# MotorControl.net
KiCad netlist of a schematic drawn in Altium Designer
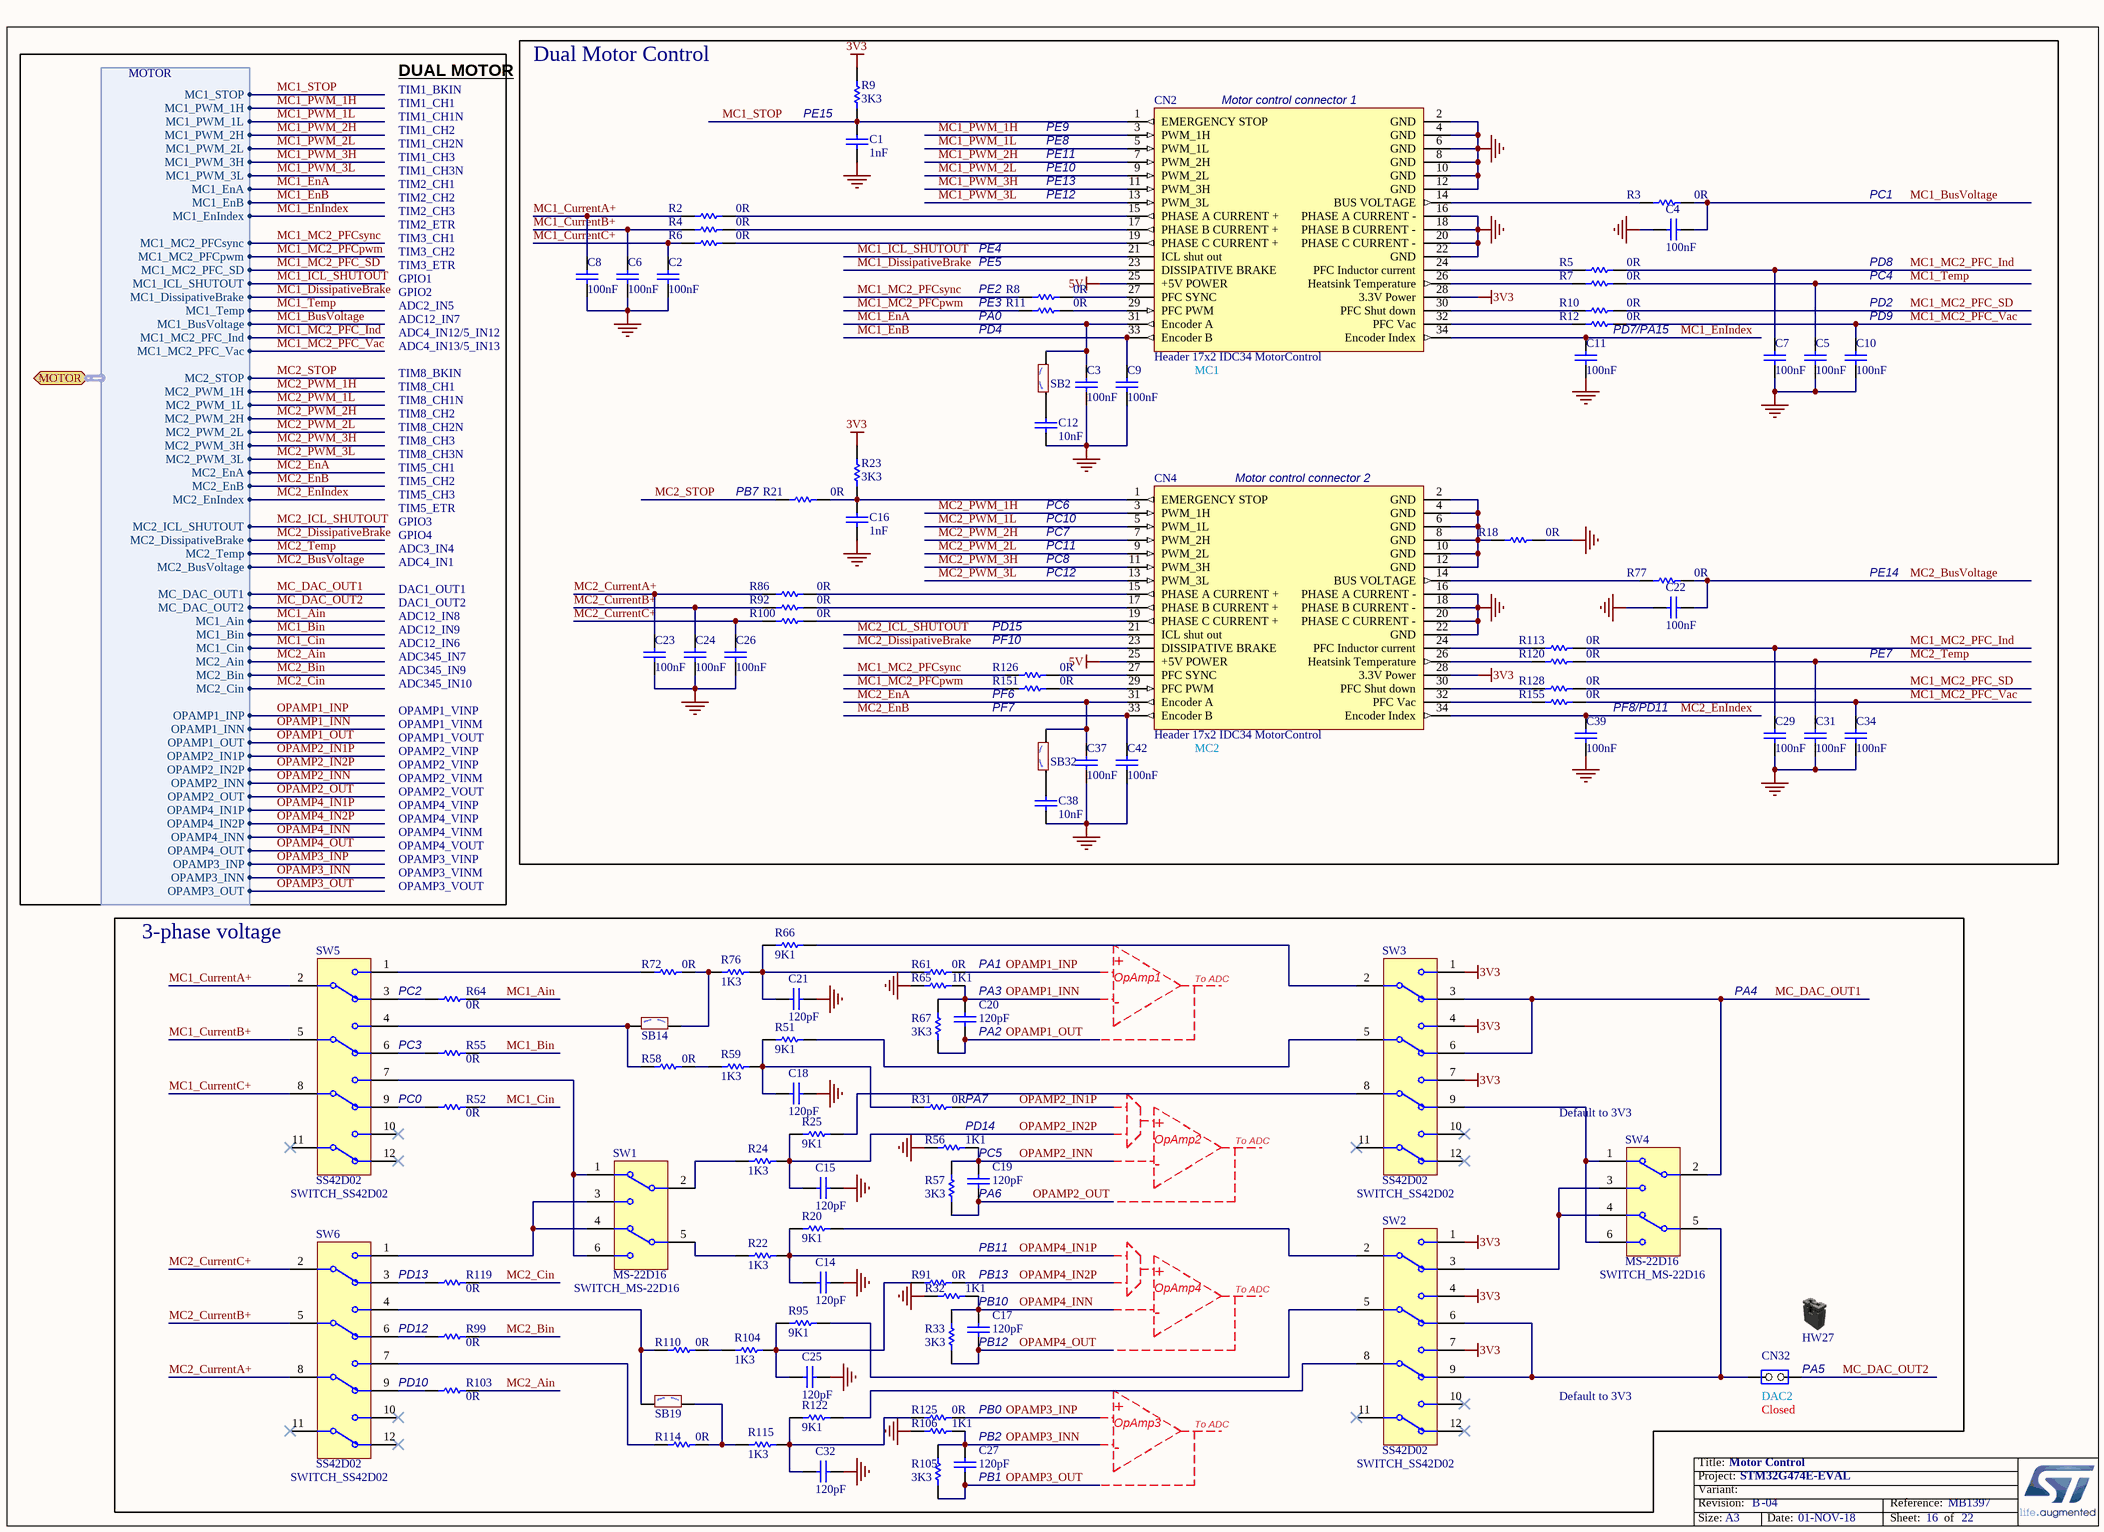
[diagram p0: MotorControl.SchDoc]

(export (version "E")
  (design (tool "Eeschema 10.0.6"))
  (components
    (comp (ref "C1")
      (value "1nF")
      (footprint "C0402")
      (description "Capacitor, MLCC, 1nF, 16V, X7R, 10%, 0402, T=0.5mm")
      (fields
        (field (name "INTERNAL_PART_NUMBER") "MCD-00198")
        (field (name "MANUFACTURER_PART_NUMBER") "CC0402KRX7R7BB102")
        (field (name "PROVIDED_BY") "SUBCO")
      )
      (libsource (lib "MCD_PARTS_database") (part "Capacitor"))
    )
    (comp (ref "C2")
      (value "100nF")
      (footprint "C0402")
      (description "Capacitor, MLCC, 100nF, 16V, X7R, 10%, 0402, T=0.5mm")
      (fields
        (field (name "INTERNAL_PART_NUMBER") "MCD-00006")
        (field (name "MANUFACTURER_PART_NUMBER") "CC0402KRX7R7BB104")
        (field (name "PROVIDED_BY") "SUBCO")
      )
      (libsource (lib "MCD_PARTS_database") (part "Capacitor"))
    )
    (comp (ref "C3")
      (value "100nF")
      (footprint "C0402")
      (description "Capacitor, MLCC, 100nF, 16V, X7R, 10%, 0402, T=0.5mm")
      (fields
        (field (name "INTERNAL_PART_NUMBER") "MCD-00006")
        (field (name "MANUFACTURER_PART_NUMBER") "CC0402KRX7R7BB104")
        (field (name "PROVIDED_BY") "SUBCO")
      )
      (libsource (lib "MCD_PARTS_database") (part "Capacitor"))
    )
    (comp (ref "C4")
      (value "100nF")
      (footprint "C0402")
      (description "Capacitor, MLCC, 100nF, 16V, X7R, 10%, 0402, T=0.5mm")
      (fields
        (field (name "INTERNAL_PART_NUMBER") "MCD-00006")
        (field (name "MANUFACTURER_PART_NUMBER") "CC0402KRX7R7BB104")
        (field (name "PROVIDED_BY") "SUBCO")
      )
      (libsource (lib "MCD_PARTS_database") (part "Capacitor"))
    )
    (comp (ref "C5")
      (value "100nF")
      (footprint "C0402")
      (description "Capacitor, MLCC, 100nF, 16V, X7R, 10%, 0402, T=0.5mm")
      (fields
        (field (name "INTERNAL_PART_NUMBER") "MCD-00006")
        (field (name "MANUFACTURER_PART_NUMBER") "CC0402KRX7R7BB104")
        (field (name "PROVIDED_BY") "SUBCO")
      )
      (libsource (lib "MCD_PARTS_database") (part "Capacitor"))
    )
    (comp (ref "C6")
      (value "100nF")
      (footprint "C0402")
      (description "Capacitor, MLCC, 100nF, 16V, X7R, 10%, 0402, T=0.5mm")
      (fields
        (field (name "INTERNAL_PART_NUMBER") "MCD-00006")
        (field (name "MANUFACTURER_PART_NUMBER") "CC0402KRX7R7BB104")
        (field (name "PROVIDED_BY") "SUBCO")
      )
      (libsource (lib "MCD_PARTS_database") (part "Capacitor"))
    )
    (comp (ref "C7")
      (value "100nF")
      (footprint "C0402")
      (description "Capacitor, MLCC, 100nF, 16V, X7R, 10%, 0402, T=0.5mm")
      (fields
        (field (name "INTERNAL_PART_NUMBER") "MCD-00006")
        (field (name "MANUFACTURER_PART_NUMBER") "CC0402KRX7R7BB104")
        (field (name "PROVIDED_BY") "SUBCO")
      )
      (libsource (lib "MCD_PARTS_database") (part "Capacitor"))
    )
    (comp (ref "C8")
      (value "100nF")
      (footprint "C0402")
      (description "Capacitor, MLCC, 100nF, 16V, X7R, 10%, 0402, T=0.5mm")
      (fields
        (field (name "INTERNAL_PART_NUMBER") "MCD-00006")
        (field (name "MANUFACTURER_PART_NUMBER") "CC0402KRX7R7BB104")
        (field (name "PROVIDED_BY") "SUBCO")
      )
      (libsource (lib "MCD_PARTS_database") (part "Capacitor"))
    )
    (comp (ref "C9")
      (value "100nF")
      (footprint "C0402")
      (description "Capacitor, MLCC, 100nF, 16V, X7R, 10%, 0402, T=0.5mm")
      (fields
        (field (name "INTERNAL_PART_NUMBER") "MCD-00006")
        (field (name "MANUFACTURER_PART_NUMBER") "CC0402KRX7R7BB104")
        (field (name "PROVIDED_BY") "SUBCO")
      )
      (libsource (lib "MCD_PARTS_database") (part "Capacitor"))
    )
    (comp (ref "C10")
      (value "100nF")
      (footprint "C0402")
      (description "Capacitor, MLCC, 100nF, 16V, X7R, 10%, 0402, T=0.5mm")
      (fields
        (field (name "INTERNAL_PART_NUMBER") "MCD-00006")
        (field (name "MANUFACTURER_PART_NUMBER") "CC0402KRX7R7BB104")
        (field (name "PROVIDED_BY") "SUBCO")
      )
      (libsource (lib "MCD_PARTS_database") (part "Capacitor"))
    )
    (comp (ref "C11")
      (value "100nF")
      (footprint "C0402")
      (description "Capacitor, MLCC, 100nF, 16V, X7R, 10%, 0402, T=0.5mm")
      (fields
        (field (name "INTERNAL_PART_NUMBER") "MCD-00006")
        (field (name "MANUFACTURER_PART_NUMBER") "CC0402KRX7R7BB104")
        (field (name "PROVIDED_BY") "SUBCO")
      )
      (libsource (lib "MCD_PARTS_database") (part "Capacitor"))
    )
    (comp (ref "C12")
      (value "10nF")
      (footprint "C0402")
      (description "Capacitor, MLCC, 10nF, 16V, X7R, 10%, 0402, T=0.5mm")
      (fields
        (field (name "INTERNAL_PART_NUMBER") "MCD-00011")
        (field (name "MANUFACTURER_PART_NUMBER") "CC0402KRX7R7BB103")
        (field (name "PROVIDED_BY") "SUBCO")
      )
      (libsource (lib "MCD_PARTS_database") (part "Capacitor"))
    )
    (comp (ref "C14")
      (value "120pF")
      (footprint "C0603")
      (description "Capacitor,120pF,50V,NPO,5%,0603")
      (fields
        (field (name "INTERNAL_PART_NUMBER") "MCD-01188")
        (field (name "MANUFACTURER_PART_NUMBER") "CC0603JRNPO9BN121")
        (field (name "PROVIDED_BY") "SUBCO")
      )
      (libsource (lib "MCD_PARTS_database") (part "Capacitor"))
    )
    (comp (ref "C15")
      (value "120pF")
      (footprint "C0603")
      (description "Capacitor,120pF,50V,NPO,5%,0603")
      (fields
        (field (name "INTERNAL_PART_NUMBER") "MCD-01188")
        (field (name "MANUFACTURER_PART_NUMBER") "CC0603JRNPO9BN121")
        (field (name "PROVIDED_BY") "SUBCO")
      )
      (libsource (lib "MCD_PARTS_database") (part "Capacitor"))
    )
    (comp (ref "C16")
      (value "1nF")
      (footprint "C0402")
      (description "Capacitor, MLCC, 1nF, 16V, X7R, 10%, 0402, T=0.5mm")
      (fields
        (field (name "INTERNAL_PART_NUMBER") "MCD-00198")
        (field (name "MANUFACTURER_PART_NUMBER") "CC0402KRX7R7BB102")
        (field (name "PROVIDED_BY") "SUBCO")
      )
      (libsource (lib "MCD_PARTS_database") (part "Capacitor"))
    )
    (comp (ref "C17")
      (value "120pF")
      (footprint "C0603")
      (description "Capacitor,120pF,50V,NPO,5%,0603")
      (fields
        (field (name "INTERNAL_PART_NUMBER") "MCD-01188")
        (field (name "MANUFACTURER_PART_NUMBER") "CC0603JRNPO9BN121")
        (field (name "PROVIDED_BY") "SUBCO")
      )
      (libsource (lib "MCD_PARTS_database") (part "Capacitor"))
    )
    (comp (ref "C18")
      (value "120pF")
      (footprint "C0603")
      (description "Capacitor,120pF,50V,NPO,5%,0603")
      (fields
        (field (name "INTERNAL_PART_NUMBER") "MCD-01188")
        (field (name "MANUFACTURER_PART_NUMBER") "CC0603JRNPO9BN121")
        (field (name "PROVIDED_BY") "SUBCO")
      )
      (libsource (lib "MCD_PARTS_database") (part "Capacitor"))
    )
    (comp (ref "C19")
      (value "120pF")
      (footprint "C0603")
      (description "Capacitor,120pF,50V,NPO,5%,0603")
      (fields
        (field (name "INTERNAL_PART_NUMBER") "MCD-01188")
        (field (name "MANUFACTURER_PART_NUMBER") "CC0603JRNPO9BN121")
        (field (name "PROVIDED_BY") "SUBCO")
      )
      (libsource (lib "MCD_PARTS_database") (part "Capacitor"))
    )
    (comp (ref "C20")
      (value "120pF")
      (footprint "C0603")
      (description "Capacitor,120pF,50V,NPO,5%,0603")
      (fields
        (field (name "INTERNAL_PART_NUMBER") "MCD-01188")
        (field (name "MANUFACTURER_PART_NUMBER") "CC0603JRNPO9BN121")
        (field (name "PROVIDED_BY") "SUBCO")
      )
      (libsource (lib "MCD_PARTS_database") (part "Capacitor"))
    )
    (comp (ref "C21")
      (value "120pF")
      (footprint "C0603")
      (description "Capacitor,120pF,50V,NPO,5%,0603")
      (fields
        (field (name "INTERNAL_PART_NUMBER") "MCD-01188")
        (field (name "MANUFACTURER_PART_NUMBER") "CC0603JRNPO9BN121")
        (field (name "PROVIDED_BY") "SUBCO")
      )
      (libsource (lib "MCD_PARTS_database") (part "Capacitor"))
    )
    (comp (ref "C22")
      (value "100nF")
      (footprint "C0402")
      (description "Capacitor, MLCC, 100nF, 16V, X7R, 10%, 0402, T=0.5mm")
      (fields
        (field (name "INTERNAL_PART_NUMBER") "MCD-00006")
        (field (name "MANUFACTURER_PART_NUMBER") "CC0402KRX7R7BB104")
        (field (name "PROVIDED_BY") "SUBCO")
      )
      (libsource (lib "MCD_PARTS_database") (part "Capacitor"))
    )
    (comp (ref "C23")
      (value "100nF")
      (footprint "C0402")
      (description "Capacitor, MLCC, 100nF, 16V, X7R, 10%, 0402, T=0.5mm")
      (fields
        (field (name "INTERNAL_PART_NUMBER") "MCD-00006")
        (field (name "MANUFACTURER_PART_NUMBER") "CC0402KRX7R7BB104")
        (field (name "PROVIDED_BY") "SUBCO")
      )
      (libsource (lib "MCD_PARTS_database") (part "Capacitor"))
    )
    (comp (ref "C24")
      (value "100nF")
      (footprint "C0402")
      (description "Capacitor, MLCC, 100nF, 16V, X7R, 10%, 0402, T=0.5mm")
      (fields
        (field (name "INTERNAL_PART_NUMBER") "MCD-00006")
        (field (name "MANUFACTURER_PART_NUMBER") "CC0402KRX7R7BB104")
        (field (name "PROVIDED_BY") "SUBCO")
      )
      (libsource (lib "MCD_PARTS_database") (part "Capacitor"))
    )
    (comp (ref "C25")
      (value "120pF")
      (footprint "C0603")
      (description "Capacitor,120pF,50V,NPO,5%,0603")
      (fields
        (field (name "INTERNAL_PART_NUMBER") "MCD-01188")
        (field (name "MANUFACTURER_PART_NUMBER") "CC0603JRNPO9BN121")
        (field (name "PROVIDED_BY") "SUBCO")
      )
      (libsource (lib "MCD_PARTS_database") (part "Capacitor"))
    )
    (comp (ref "C26")
      (value "100nF")
      (footprint "C0402")
      (description "Capacitor, MLCC, 100nF, 16V, X7R, 10%, 0402, T=0.5mm")
      (fields
        (field (name "INTERNAL_PART_NUMBER") "MCD-00006")
        (field (name "MANUFACTURER_PART_NUMBER") "CC0402KRX7R7BB104")
        (field (name "PROVIDED_BY") "SUBCO")
      )
      (libsource (lib "MCD_PARTS_database") (part "Capacitor"))
    )
    (comp (ref "C27")
      (value "120pF")
      (footprint "C0603")
      (description "Capacitor,120pF,50V,NPO,5%,0603")
      (fields
        (field (name "INTERNAL_PART_NUMBER") "MCD-01188")
        (field (name "MANUFACTURER_PART_NUMBER") "CC0603JRNPO9BN121")
        (field (name "PROVIDED_BY") "SUBCO")
      )
      (libsource (lib "MCD_PARTS_database") (part "Capacitor"))
    )
    (comp (ref "C29")
      (value "100nF")
      (footprint "C0402")
      (description "Capacitor, MLCC, 100nF, 16V, X7R, 10%, 0402, T=0.5mm")
      (fields
        (field (name "INTERNAL_PART_NUMBER") "MCD-00006")
        (field (name "MANUFACTURER_PART_NUMBER") "CC0402KRX7R7BB104")
        (field (name "PROVIDED_BY") "SUBCO")
      )
      (libsource (lib "MCD_PARTS_database") (part "Capacitor"))
    )
    (comp (ref "C31")
      (value "100nF")
      (footprint "C0402")
      (description "Capacitor, MLCC, 100nF, 16V, X7R, 10%, 0402, T=0.5mm")
      (fields
        (field (name "INTERNAL_PART_NUMBER") "MCD-00006")
        (field (name "MANUFACTURER_PART_NUMBER") "CC0402KRX7R7BB104")
        (field (name "PROVIDED_BY") "SUBCO")
      )
      (libsource (lib "MCD_PARTS_database") (part "Capacitor"))
    )
    (comp (ref "C32")
      (value "120pF")
      (footprint "C0603")
      (description "Capacitor,120pF,50V,NPO,5%,0603")
      (fields
        (field (name "INTERNAL_PART_NUMBER") "MCD-01188")
        (field (name "MANUFACTURER_PART_NUMBER") "CC0603JRNPO9BN121")
        (field (name "PROVIDED_BY") "SUBCO")
      )
      (libsource (lib "MCD_PARTS_database") (part "Capacitor"))
    )
    (comp (ref "C34")
      (value "100nF")
      (footprint "C0402")
      (description "Capacitor, MLCC, 100nF, 16V, X7R, 10%, 0402, T=0.5mm")
      (fields
        (field (name "INTERNAL_PART_NUMBER") "MCD-00006")
        (field (name "MANUFACTURER_PART_NUMBER") "CC0402KRX7R7BB104")
        (field (name "PROVIDED_BY") "SUBCO")
      )
      (libsource (lib "MCD_PARTS_database") (part "Capacitor"))
    )
    (comp (ref "C37")
      (value "100nF")
      (footprint "C0402")
      (description "Capacitor, MLCC, 100nF, 16V, X7R, 10%, 0402, T=0.5mm")
      (fields
        (field (name "INTERNAL_PART_NUMBER") "MCD-00006")
        (field (name "MANUFACTURER_PART_NUMBER") "CC0402KRX7R7BB104")
        (field (name "PROVIDED_BY") "SUBCO")
      )
      (libsource (lib "MCD_PARTS_database") (part "Capacitor"))
    )
    (comp (ref "C38")
      (value "10nF")
      (footprint "C0402")
      (description "Capacitor, MLCC, 10nF, 16V, X7R, 10%, 0402, T=0.5mm")
      (fields
        (field (name "INTERNAL_PART_NUMBER") "MCD-00011")
        (field (name "MANUFACTURER_PART_NUMBER") "CC0402KRX7R7BB103")
        (field (name "PROVIDED_BY") "SUBCO")
      )
      (libsource (lib "MCD_PARTS_database") (part "Capacitor"))
    )
    (comp (ref "C39")
      (value "100nF")
      (footprint "C0402")
      (description "Capacitor, MLCC, 100nF, 16V, X7R, 10%, 0402, T=0.5mm")
      (fields
        (field (name "INTERNAL_PART_NUMBER") "MCD-00006")
        (field (name "MANUFACTURER_PART_NUMBER") "CC0402KRX7R7BB104")
        (field (name "PROVIDED_BY") "SUBCO")
      )
      (libsource (lib "MCD_PARTS_database") (part "Capacitor"))
    )
    (comp (ref "C42")
      (value "100nF")
      (footprint "C0402")
      (description "Capacitor, MLCC, 100nF, 16V, X7R, 10%, 0402, T=0.5mm")
      (fields
        (field (name "INTERNAL_PART_NUMBER") "MCD-00006")
        (field (name "MANUFACTURER_PART_NUMBER") "CC0402KRX7R7BB104")
        (field (name "PROVIDED_BY") "SUBCO")
      )
      (libsource (lib "MCD_PARTS_database") (part "Capacitor"))
    )
    (comp (ref "CN2")
      (value "Header 17x2 IDC34 MotorControl")
      (footprint "CON_SAMTEC_TST-117-01-T-D")
      (description "Header, 17x2, 2.54mm, VR, TH, Height 8.89mm/2.92mm, shrouded")
      (fields
        (field (name "INTERNAL_PART_NUMBER") "MCD-00583")
        (field (name "MANUFACTURER_PART_NUMBER") "TST-117-01-T-D")
        (field (name "PROVIDED_BY") "SUBCO")
      )
      (libsource (lib "MCD_PARTS_database") (part "Header 17x2 IDC34 MotorControl"))
    )
    (comp (ref "CN4")
      (value "Header 17x2 IDC34 MotorControl")
      (footprint "CON_SAMTEC_TST-117-01-T-D")
      (description "Header, 17x2, 2.54mm, VR, TH, Height 8.89mm/2.92mm, shrouded")
      (fields
        (field (name "INTERNAL_PART_NUMBER") "MCD-00583")
        (field (name "MANUFACTURER_PART_NUMBER") "TST-117-01-T-D")
        (field (name "PROVIDED_BY") "SUBCO")
      )
      (libsource (lib "MCD_PARTS_database") (part "Header 17x2 IDC34 MotorControl"))
    )
    (comp (ref "CN32")
      (value "Jumper_Header 2x1")
      (footprint "CON_SAMTEC_TSW-102-07-G-S")
      (description "Header, 2x1, 2,54mm, VR, TH, Height 5.84mm/2.54mm")
      (fields
        (field (name "INTERNAL_PART_NUMBER") "MCD-00045")
        (field (name "MANUFACTURER_PART_NUMBER") "TSW-102-07-x-S")
        (field (name "PROVIDED_BY") "SUBCO")
      )
      (libsource (lib "MCD_PARTS_database") (part "Jumper_Header 2x1"))
    )
    (comp (ref "HW27")
      (value "Shunt Black 2.54mm")
      (description "SHUNT 2.54mm BLACK")
      (fields
        (field (name "INTERNAL_PART_NUMBER") "MCD-00043")
        (field (name "MANUFACTURER_PART_NUMBER") "SNT-100-BK-G")
        (field (name "PROVIDED_BY") "SUBCO")
      )
      (libsource (lib "MCD_PARTS_database") (part "Shunt Black 2.54mm"))
    )
    (comp (ref "R2")
      (value "0R")
      (footprint "R0603")
      (description "Resistor,0R,0603,5%,1/10W")
      (fields
        (field (name "INTERNAL_PART_NUMBER") "MCD-00056")
        (field (name "MANUFACTURER_PART_NUMBER") "RC0603JR-070RL")
        (field (name "PROVIDED_BY") "SUBCO")
      )
      (libsource (lib "MCD_PARTS_database") (part "Resistor"))
    )
    (comp (ref "R3")
      (value "0R")
      (footprint "R0603")
      (description "Resistor,0R,0603,5%,1/10W")
      (fields
        (field (name "INTERNAL_PART_NUMBER") "MCD-00056")
        (field (name "MANUFACTURER_PART_NUMBER") "RC0603JR-070RL")
        (field (name "PROVIDED_BY") "SUBCO")
      )
      (libsource (lib "MCD_PARTS_database") (part "Resistor"))
    )
    (comp (ref "R4")
      (value "0R")
      (footprint "R0603")
      (description "Resistor,0R,0603,5%,1/10W")
      (fields
        (field (name "INTERNAL_PART_NUMBER") "MCD-00056")
        (field (name "MANUFACTURER_PART_NUMBER") "RC0603JR-070RL")
        (field (name "PROVIDED_BY") "SUBCO")
      )
      (libsource (lib "MCD_PARTS_database") (part "Resistor"))
    )
    (comp (ref "R5")
      (value "0R")
      (footprint "R0603")
      (description "Resistor,0R,0603,5%,1/10W")
      (fields
        (field (name "INTERNAL_PART_NUMBER") "MCD-00056")
        (field (name "MANUFACTURER_PART_NUMBER") "RC0603JR-070RL")
        (field (name "PROVIDED_BY") "SUBCO")
      )
      (libsource (lib "MCD_PARTS_database") (part "Resistor"))
    )
    (comp (ref "R6")
      (value "0R")
      (footprint "R0603")
      (description "Resistor,0R,0603,5%,1/10W")
      (fields
        (field (name "INTERNAL_PART_NUMBER") "MCD-00056")
        (field (name "MANUFACTURER_PART_NUMBER") "RC0603JR-070RL")
        (field (name "PROVIDED_BY") "SUBCO")
      )
      (libsource (lib "MCD_PARTS_database") (part "Resistor"))
    )
    (comp (ref "R7")
      (value "0R")
      (footprint "R0603")
      (description "Resistor,0R,0603,5%,1/10W")
      (fields
        (field (name "INTERNAL_PART_NUMBER") "MCD-00056")
        (field (name "MANUFACTURER_PART_NUMBER") "RC0603JR-070RL")
        (field (name "PROVIDED_BY") "SUBCO")
      )
      (libsource (lib "MCD_PARTS_database") (part "Resistor"))
    )
    (comp (ref "R8")
      (value "0R")
      (footprint "R0603")
      (description "Resistor,0R,0603,5%,1/10W")
      (fields
        (field (name "INTERNAL_PART_NUMBER") "MCD-00056")
        (field (name "MANUFACTURER_PART_NUMBER") "RC0603JR-070RL")
        (field (name "PROVIDED_BY") "SUBCO")
      )
      (libsource (lib "MCD_PARTS_database") (part "Resistor"))
    )
    (comp (ref "R9")
      (value "3K3")
      (footprint "R0402")
      (description "Resistor,3K3,0402,1%,1/16W")
      (fields
        (field (name "INTERNAL_PART_NUMBER") "MCD-00184")
        (field (name "MANUFACTURER_PART_NUMBER") "RC0402FR-073K3L")
        (field (name "PROVIDED_BY") "SUBCO")
      )
      (libsource (lib "MCD_PARTS_database") (part "Resistor"))
    )
    (comp (ref "R10")
      (value "0R")
      (footprint "R0603")
      (description "Resistor,0R,0603,5%,1/10W")
      (fields
        (field (name "INTERNAL_PART_NUMBER") "MCD-00056")
        (field (name "MANUFACTURER_PART_NUMBER") "RC0603JR-070RL")
        (field (name "PROVIDED_BY") "SUBCO")
      )
      (libsource (lib "MCD_PARTS_database") (part "Resistor"))
    )
    (comp (ref "R11")
      (value "0R")
      (footprint "R0603")
      (description "Resistor,0R,0603,5%,1/10W")
      (fields
        (field (name "INTERNAL_PART_NUMBER") "MCD-00056")
        (field (name "MANUFACTURER_PART_NUMBER") "RC0603JR-070RL")
        (field (name "PROVIDED_BY") "SUBCO")
      )
      (libsource (lib "MCD_PARTS_database") (part "Resistor"))
    )
    (comp (ref "R12")
      (value "0R")
      (footprint "R0603")
      (description "Resistor,0R,0603,5%,1/10W")
      (fields
        (field (name "INTERNAL_PART_NUMBER") "MCD-00056")
        (field (name "MANUFACTURER_PART_NUMBER") "RC0603JR-070RL")
        (field (name "PROVIDED_BY") "SUBCO")
      )
      (libsource (lib "MCD_PARTS_database") (part "Resistor"))
    )
    (comp (ref "R18")
      (value "0R")
      (footprint "R0603")
      (description "Resistor,0R,0603,5%,1/10W")
      (fields
        (field (name "INTERNAL_PART_NUMBER") "MCD-00056")
        (field (name "MANUFACTURER_PART_NUMBER") "RC0603JR-070RL")
        (field (name "PROVIDED_BY") "SUBCO")
      )
      (libsource (lib "MCD_PARTS_database") (part "Resistor"))
    )
    (comp (ref "R20")
      (value "9K1")
      (footprint "R0603")
      (description "Resistor,9K1,0603,1%,1/10W")
      (fields
        (field (name "INTERNAL_PART_NUMBER") "MCD-00540")
        (field (name "MANUFACTURER_PART_NUMBER") "RC0603FR-079K1L")
        (field (name "PROVIDED_BY") "SUBCO")
      )
      (libsource (lib "MCD_PARTS_database") (part "Resistor"))
    )
    (comp (ref "R21")
      (value "0R")
      (footprint "R0603")
      (description "Resistor,0R,0603,5%,1/10W")
      (fields
        (field (name "INTERNAL_PART_NUMBER") "MCD-00056")
        (field (name "MANUFACTURER_PART_NUMBER") "RC0603JR-070RL")
        (field (name "PROVIDED_BY") "SUBCO")
      )
      (libsource (lib "MCD_PARTS_database") (part "Resistor"))
    )
    (comp (ref "R22")
      (value "1K3")
      (footprint "R0603")
      (description "Resistor,1K3,0603,1%,1/10W")
      (fields
        (field (name "INTERNAL_PART_NUMBER") "MCD-00382")
        (field (name "MANUFACTURER_PART_NUMBER") "RC0603FR-071K3L")
        (field (name "PROVIDED_BY") "SUBCO")
      )
      (libsource (lib "MCD_PARTS_database") (part "Resistor"))
    )
    (comp (ref "R23")
      (value "3K3")
      (footprint "R0402")
      (description "Resistor,3K3,0402,1%,1/16W")
      (fields
        (field (name "INTERNAL_PART_NUMBER") "MCD-00184")
        (field (name "MANUFACTURER_PART_NUMBER") "RC0402FR-073K3L")
        (field (name "PROVIDED_BY") "SUBCO")
      )
      (libsource (lib "MCD_PARTS_database") (part "Resistor"))
    )
    (comp (ref "R24")
      (value "1K3")
      (footprint "R0603")
      (description "Resistor,1K3,0603,1%,1/10W")
      (fields
        (field (name "INTERNAL_PART_NUMBER") "MCD-00382")
        (field (name "MANUFACTURER_PART_NUMBER") "RC0603FR-071K3L")
        (field (name "PROVIDED_BY") "SUBCO")
      )
      (libsource (lib "MCD_PARTS_database") (part "Resistor"))
    )
    (comp (ref "R25")
      (value "9K1")
      (footprint "R0603")
      (description "Resistor,9K1,0603,1%,1/10W")
      (fields
        (field (name "INTERNAL_PART_NUMBER") "MCD-00540")
        (field (name "MANUFACTURER_PART_NUMBER") "RC0603FR-079K1L")
        (field (name "PROVIDED_BY") "SUBCO")
      )
      (libsource (lib "MCD_PARTS_database") (part "Resistor"))
    )
    (comp (ref "R31")
      (value "0R")
      (footprint "R0603")
      (description "Resistor,0R,0603,5%,1/10W")
      (fields
        (field (name "INTERNAL_PART_NUMBER") "MCD-00056")
        (field (name "MANUFACTURER_PART_NUMBER") "RC0603JR-070RL")
        (field (name "PROVIDED_BY") "SUBCO")
      )
      (libsource (lib "MCD_PARTS_database") (part "Resistor"))
    )
    (comp (ref "R32")
      (value "1K1")
      (footprint "R0603")
      (description "Resistor,1K1,0603,1%,1/10W")
      (fields
        (field (name "INTERNAL_PART_NUMBER") "MCD-00364")
        (field (name "MANUFACTURER_PART_NUMBER") "RC0603FR-071K1L")
        (field (name "PROVIDED_BY") "SUBCO")
      )
      (libsource (lib "MCD_PARTS_database") (part "Resistor"))
    )
    (comp (ref "R33")
      (value "3K3")
      (footprint "R0603")
      (description "Resistor,3K3,0603,1%,1/10W")
      (fields
        (field (name "INTERNAL_PART_NUMBER") "MCD-00352")
        (field (name "MANUFACTURER_PART_NUMBER") "RC0603FR-073K3L")
        (field (name "PROVIDED_BY") "SUBCO")
      )
      (libsource (lib "MCD_PARTS_database") (part "Resistor"))
    )
    (comp (ref "R51")
      (value "9K1")
      (footprint "R0603")
      (description "Resistor,9K1,0603,1%,1/10W")
      (fields
        (field (name "INTERNAL_PART_NUMBER") "MCD-00540")
        (field (name "MANUFACTURER_PART_NUMBER") "RC0603FR-079K1L")
        (field (name "PROVIDED_BY") "SUBCO")
      )
      (libsource (lib "MCD_PARTS_database") (part "Resistor"))
    )
    (comp (ref "R52")
      (value "0R")
      (footprint "R0603")
      (description "Resistor,0R,0603,5%,1/10W")
      (fields
        (field (name "INTERNAL_PART_NUMBER") "MCD-00056")
        (field (name "MANUFACTURER_PART_NUMBER") "RC0603JR-070RL")
        (field (name "PROVIDED_BY") "SUBCO")
      )
      (libsource (lib "MCD_PARTS_database") (part "Resistor"))
    )
    (comp (ref "R55")
      (value "0R")
      (footprint "R0603")
      (description "Resistor,0R,0603,5%,1/10W")
      (fields
        (field (name "INTERNAL_PART_NUMBER") "MCD-00056")
        (field (name "MANUFACTURER_PART_NUMBER") "RC0603JR-070RL")
        (field (name "PROVIDED_BY") "SUBCO")
      )
      (libsource (lib "MCD_PARTS_database") (part "Resistor"))
    )
    (comp (ref "R56")
      (value "1K1")
      (footprint "R0603")
      (description "Resistor,1K1,0603,1%,1/10W")
      (fields
        (field (name "INTERNAL_PART_NUMBER") "MCD-00364")
        (field (name "MANUFACTURER_PART_NUMBER") "RC0603FR-071K1L")
        (field (name "PROVIDED_BY") "SUBCO")
      )
      (libsource (lib "MCD_PARTS_database") (part "Resistor"))
    )
    (comp (ref "R57")
      (value "3K3")
      (footprint "R0603")
      (description "Resistor,3K3,0603,1%,1/10W")
      (fields
        (field (name "INTERNAL_PART_NUMBER") "MCD-00352")
        (field (name "MANUFACTURER_PART_NUMBER") "RC0603FR-073K3L")
        (field (name "PROVIDED_BY") "SUBCO")
      )
      (libsource (lib "MCD_PARTS_database") (part "Resistor"))
    )
    (comp (ref "R58")
      (value "0R")
      (footprint "R0603")
      (description "Resistor,0R,0603,5%,1/10W")
      (fields
        (field (name "INTERNAL_PART_NUMBER") "MCD-00056")
        (field (name "MANUFACTURER_PART_NUMBER") "RC0603JR-070RL")
        (field (name "PROVIDED_BY") "SUBCO")
      )
      (libsource (lib "MCD_PARTS_database") (part "Resistor"))
    )
    (comp (ref "R59")
      (value "1K3")
      (footprint "R0603")
      (description "Resistor,1K3,0603,1%,1/10W")
      (fields
        (field (name "INTERNAL_PART_NUMBER") "MCD-00382")
        (field (name "MANUFACTURER_PART_NUMBER") "RC0603FR-071K3L")
        (field (name "PROVIDED_BY") "SUBCO")
      )
      (libsource (lib "MCD_PARTS_database") (part "Resistor"))
    )
    (comp (ref "R61")
      (value "0R")
      (footprint "R0603")
      (description "Resistor,0R,0603,5%,1/10W")
      (fields
        (field (name "INTERNAL_PART_NUMBER") "MCD-00056")
        (field (name "MANUFACTURER_PART_NUMBER") "RC0603JR-070RL")
        (field (name "PROVIDED_BY") "SUBCO")
      )
      (libsource (lib "MCD_PARTS_database") (part "Resistor"))
    )
    (comp (ref "R64")
      (value "0R")
      (footprint "R0603")
      (description "Resistor,0R,0603,5%,1/10W")
      (fields
        (field (name "INTERNAL_PART_NUMBER") "MCD-00056")
        (field (name "MANUFACTURER_PART_NUMBER") "RC0603JR-070RL")
        (field (name "PROVIDED_BY") "SUBCO")
      )
      (libsource (lib "MCD_PARTS_database") (part "Resistor"))
    )
    (comp (ref "R65")
      (value "1K1")
      (footprint "R0603")
      (description "Resistor,1K1,0603,1%,1/10W")
      (fields
        (field (name "INTERNAL_PART_NUMBER") "MCD-00364")
        (field (name "MANUFACTURER_PART_NUMBER") "RC0603FR-071K1L")
        (field (name "PROVIDED_BY") "SUBCO")
      )
      (libsource (lib "MCD_PARTS_database") (part "Resistor"))
    )
    (comp (ref "R66")
      (value "9K1")
      (footprint "R0603")
      (description "Resistor,9K1,0603,1%,1/10W")
      (fields
        (field (name "INTERNAL_PART_NUMBER") "MCD-00540")
        (field (name "MANUFACTURER_PART_NUMBER") "RC0603FR-079K1L")
        (field (name "PROVIDED_BY") "SUBCO")
      )
      (libsource (lib "MCD_PARTS_database") (part "Resistor"))
    )
    (comp (ref "R67")
      (value "3K3")
      (footprint "R0603")
      (description "Resistor,3K3,0603,1%,1/10W")
      (fields
        (field (name "INTERNAL_PART_NUMBER") "MCD-00352")
        (field (name "MANUFACTURER_PART_NUMBER") "RC0603FR-073K3L")
        (field (name "PROVIDED_BY") "SUBCO")
      )
      (libsource (lib "MCD_PARTS_database") (part "Resistor"))
    )
    (comp (ref "R72")
      (value "0R")
      (footprint "R0603")
      (description "Resistor,0R,0603,5%,1/10W")
      (fields
        (field (name "INTERNAL_PART_NUMBER") "MCD-00056")
        (field (name "MANUFACTURER_PART_NUMBER") "RC0603JR-070RL")
        (field (name "PROVIDED_BY") "SUBCO")
      )
      (libsource (lib "MCD_PARTS_database") (part "Resistor"))
    )
    (comp (ref "R76")
      (value "1K3")
      (footprint "R0603")
      (description "Resistor,1K3,0603,1%,1/10W")
      (fields
        (field (name "INTERNAL_PART_NUMBER") "MCD-00382")
        (field (name "MANUFACTURER_PART_NUMBER") "RC0603FR-071K3L")
        (field (name "PROVIDED_BY") "SUBCO")
      )
      (libsource (lib "MCD_PARTS_database") (part "Resistor"))
    )
    (comp (ref "R77")
      (value "0R")
      (footprint "R0603")
      (description "Resistor,0R,0603,5%,1/10W")
      (fields
        (field (name "INTERNAL_PART_NUMBER") "MCD-00056")
        (field (name "MANUFACTURER_PART_NUMBER") "RC0603JR-070RL")
        (field (name "PROVIDED_BY") "SUBCO")
      )
      (libsource (lib "MCD_PARTS_database") (part "Resistor"))
    )
    (comp (ref "R86")
      (value "0R")
      (footprint "R0603")
      (description "Resistor,0R,0603,5%,1/10W")
      (fields
        (field (name "INTERNAL_PART_NUMBER") "MCD-00056")
        (field (name "MANUFACTURER_PART_NUMBER") "RC0603JR-070RL")
        (field (name "PROVIDED_BY") "SUBCO")
      )
      (libsource (lib "MCD_PARTS_database") (part "Resistor"))
    )
    (comp (ref "R91")
      (value "0R")
      (footprint "R0603")
      (description "Resistor,0R,0603,5%,1/10W")
      (fields
        (field (name "INTERNAL_PART_NUMBER") "MCD-00056")
        (field (name "MANUFACTURER_PART_NUMBER") "RC0603JR-070RL")
        (field (name "PROVIDED_BY") "SUBCO")
      )
      (libsource (lib "MCD_PARTS_database") (part "Resistor"))
    )
    (comp (ref "R92")
      (value "0R")
      (footprint "R0603")
      (description "Resistor,0R,0603,5%,1/10W")
      (fields
        (field (name "INTERNAL_PART_NUMBER") "MCD-00056")
        (field (name "MANUFACTURER_PART_NUMBER") "RC0603JR-070RL")
        (field (name "PROVIDED_BY") "SUBCO")
      )
      (libsource (lib "MCD_PARTS_database") (part "Resistor"))
    )
    (comp (ref "R95")
      (value "9K1")
      (footprint "R0603")
      (description "Resistor,9K1,0603,1%,1/10W")
      (fields
        (field (name "INTERNAL_PART_NUMBER") "MCD-00540")
        (field (name "MANUFACTURER_PART_NUMBER") "RC0603FR-079K1L")
        (field (name "PROVIDED_BY") "SUBCO")
      )
      (libsource (lib "MCD_PARTS_database") (part "Resistor"))
    )
    (comp (ref "R99")
      (value "0R")
      (footprint "R0603")
      (description "Resistor,0R,0603,5%,1/10W")
      (fields
        (field (name "INTERNAL_PART_NUMBER") "MCD-00056")
        (field (name "MANUFACTURER_PART_NUMBER") "RC0603JR-070RL")
        (field (name "PROVIDED_BY") "SUBCO")
      )
      (libsource (lib "MCD_PARTS_database") (part "Resistor"))
    )
    (comp (ref "R100")
      (value "0R")
      (footprint "R0603")
      (description "Resistor,0R,0603,5%,1/10W")
      (fields
        (field (name "INTERNAL_PART_NUMBER") "MCD-00056")
        (field (name "MANUFACTURER_PART_NUMBER") "RC0603JR-070RL")
        (field (name "PROVIDED_BY") "SUBCO")
      )
      (libsource (lib "MCD_PARTS_database") (part "Resistor"))
    )
    (comp (ref "R103")
      (value "0R")
      (footprint "R0603")
      (description "Resistor,0R,0603,5%,1/10W")
      (fields
        (field (name "INTERNAL_PART_NUMBER") "MCD-00056")
        (field (name "MANUFACTURER_PART_NUMBER") "RC0603JR-070RL")
        (field (name "PROVIDED_BY") "SUBCO")
      )
      (libsource (lib "MCD_PARTS_database") (part "Resistor"))
    )
    (comp (ref "R104")
      (value "1K3")
      (footprint "R0603")
      (description "Resistor,1K3,0603,1%,1/10W")
      (fields
        (field (name "INTERNAL_PART_NUMBER") "MCD-00382")
        (field (name "MANUFACTURER_PART_NUMBER") "RC0603FR-071K3L")
        (field (name "PROVIDED_BY") "SUBCO")
      )
      (libsource (lib "MCD_PARTS_database") (part "Resistor"))
    )
    (comp (ref "R105")
      (value "3K3")
      (footprint "R0603")
      (description "Resistor,3K3,0603,1%,1/10W")
      (fields
        (field (name "INTERNAL_PART_NUMBER") "MCD-00352")
        (field (name "MANUFACTURER_PART_NUMBER") "RC0603FR-073K3L")
        (field (name "PROVIDED_BY") "SUBCO")
      )
      (libsource (lib "MCD_PARTS_database") (part "Resistor"))
    )
    (comp (ref "R106")
      (value "1K1")
      (footprint "R0603")
      (description "Resistor,1K1,0603,1%,1/10W")
      (fields
        (field (name "INTERNAL_PART_NUMBER") "MCD-00364")
        (field (name "MANUFACTURER_PART_NUMBER") "RC0603FR-071K1L")
        (field (name "PROVIDED_BY") "SUBCO")
      )
      (libsource (lib "MCD_PARTS_database") (part "Resistor"))
    )
    (comp (ref "R110")
      (value "0R")
      (footprint "R0603")
      (description "Resistor,0R,0603,5%,1/10W")
      (fields
        (field (name "INTERNAL_PART_NUMBER") "MCD-00056")
        (field (name "MANUFACTURER_PART_NUMBER") "RC0603JR-070RL")
        (field (name "PROVIDED_BY") "SUBCO")
      )
      (libsource (lib "MCD_PARTS_database") (part "Resistor"))
    )
    (comp (ref "R113")
      (value "0R")
      (footprint "R0603")
      (description "Resistor,0R,0603,5%,1/10W")
      (fields
        (field (name "INTERNAL_PART_NUMBER") "MCD-00056")
        (field (name "MANUFACTURER_PART_NUMBER") "RC0603JR-070RL")
        (field (name "PROVIDED_BY") "SUBCO")
      )
      (libsource (lib "MCD_PARTS_database") (part "Resistor"))
    )
    (comp (ref "R114")
      (value "0R")
      (footprint "R0603")
      (description "Resistor,0R,0603,5%,1/10W")
      (fields
        (field (name "INTERNAL_PART_NUMBER") "MCD-00056")
        (field (name "MANUFACTURER_PART_NUMBER") "RC0603JR-070RL")
        (field (name "PROVIDED_BY") "SUBCO")
      )
      (libsource (lib "MCD_PARTS_database") (part "Resistor"))
    )
    (comp (ref "R115")
      (value "1K3")
      (footprint "R0603")
      (description "Resistor,1K3,0603,1%,1/10W")
      (fields
        (field (name "INTERNAL_PART_NUMBER") "MCD-00382")
        (field (name "MANUFACTURER_PART_NUMBER") "RC0603FR-071K3L")
        (field (name "PROVIDED_BY") "SUBCO")
      )
      (libsource (lib "MCD_PARTS_database") (part "Resistor"))
    )
    (comp (ref "R119")
      (value "0R")
      (footprint "R0603")
      (description "Resistor,0R,0603,5%,1/10W")
      (fields
        (field (name "INTERNAL_PART_NUMBER") "MCD-00056")
        (field (name "MANUFACTURER_PART_NUMBER") "RC0603JR-070RL")
        (field (name "PROVIDED_BY") "SUBCO")
      )
      (libsource (lib "MCD_PARTS_database") (part "Resistor"))
    )
    (comp (ref "R120")
      (value "0R")
      (footprint "R0603")
      (description "Resistor,0R,0603,5%,1/10W")
      (fields
        (field (name "INTERNAL_PART_NUMBER") "MCD-00056")
        (field (name "MANUFACTURER_PART_NUMBER") "RC0603JR-070RL")
        (field (name "PROVIDED_BY") "SUBCO")
      )
      (libsource (lib "MCD_PARTS_database") (part "Resistor"))
    )
    (comp (ref "R122")
      (value "9K1")
      (footprint "R0603")
      (description "Resistor,9K1,0603,1%,1/10W")
      (fields
        (field (name "INTERNAL_PART_NUMBER") "MCD-00540")
        (field (name "MANUFACTURER_PART_NUMBER") "RC0603FR-079K1L")
        (field (name "PROVIDED_BY") "SUBCO")
      )
      (libsource (lib "MCD_PARTS_database") (part "Resistor"))
    )
    (comp (ref "R125")
      (value "0R")
      (footprint "R0603")
      (description "Resistor,0R,0603,5%,1/10W")
      (fields
        (field (name "INTERNAL_PART_NUMBER") "MCD-00056")
        (field (name "MANUFACTURER_PART_NUMBER") "RC0603JR-070RL")
        (field (name "PROVIDED_BY") "SUBCO")
      )
      (libsource (lib "MCD_PARTS_database") (part "Resistor"))
    )
    (comp (ref "R126")
      (value "0R")
      (footprint "R0603")
      (description "Resistor,0R,0603,5%,1/10W")
      (fields
        (field (name "INTERNAL_PART_NUMBER") "MCD-00056")
        (field (name "MANUFACTURER_PART_NUMBER") "RC0603JR-070RL")
        (field (name "PROVIDED_BY") "SUBCO")
      )
      (libsource (lib "MCD_PARTS_database") (part "Resistor"))
    )
    (comp (ref "R128")
      (value "0R")
      (footprint "R0603")
      (description "Resistor,0R,0603,5%,1/10W")
      (fields
        (field (name "INTERNAL_PART_NUMBER") "MCD-00056")
        (field (name "MANUFACTURER_PART_NUMBER") "RC0603JR-070RL")
        (field (name "PROVIDED_BY") "SUBCO")
      )
      (libsource (lib "MCD_PARTS_database") (part "Resistor"))
    )
    (comp (ref "R151")
      (value "0R")
      (footprint "R0603")
      (description "Resistor,0R,0603,5%,1/10W")
      (fields
        (field (name "INTERNAL_PART_NUMBER") "MCD-00056")
        (field (name "MANUFACTURER_PART_NUMBER") "RC0603JR-070RL")
        (field (name "PROVIDED_BY") "SUBCO")
      )
      (libsource (lib "MCD_PARTS_database") (part "Resistor"))
    )
    (comp (ref "R155")
      (value "0R")
      (footprint "R0603")
      (description "Resistor,0R,0603,5%,1/10W")
      (fields
        (field (name "INTERNAL_PART_NUMBER") "MCD-00056")
        (field (name "MANUFACTURER_PART_NUMBER") "RC0603JR-070RL")
        (field (name "PROVIDED_BY") "SUBCO")
      )
      (libsource (lib "MCD_PARTS_database") (part "Resistor"))
    )
    (comp (ref "SB2")
      (value "SB_OFF")
      (footprint "SOLDER-BRIDGE_R0603-0R")
      (description "Solder Bridge OFF")
      (fields
        (field (name "INTERNAL_PART_NUMBER") "MCD-00072")
        (field (name "MANUFACTURER_PART_NUMBER") "RC0603JR-070RL")
        (field (name "PROVIDED_BY") "SUBCO")
      )
      (libsource (lib "MCD_PARTS_database") (part "SB_OFF"))
    )
    (comp (ref "SB14")
      (value "SB_OFF")
      (footprint "SOLDER-BRIDGE_R0603-0R")
      (description "Solder Bridge OFF")
      (fields
        (field (name "INTERNAL_PART_NUMBER") "MCD-00072")
        (field (name "MANUFACTURER_PART_NUMBER") "RC0603JR-070RL")
        (field (name "PROVIDED_BY") "SUBCO")
      )
      (libsource (lib "") (part "SB_OFF_1"))
    )
    (comp (ref "SB19")
      (value "SB_OFF")
      (footprint "SOLDER-BRIDGE_R0603-0R")
      (description "Solder Bridge OFF")
      (fields
        (field (name "INTERNAL_PART_NUMBER") "MCD-00072")
        (field (name "MANUFACTURER_PART_NUMBER") "RC0603JR-070RL")
        (field (name "PROVIDED_BY") "SUBCO")
      )
      (libsource (lib "") (part "SB_OFF_1"))
    )
    (comp (ref "SB32")
      (value "SB_OFF")
      (footprint "SOLDER-BRIDGE_R0603-0R")
      (description "Solder Bridge OFF")
      (fields
        (field (name "INTERNAL_PART_NUMBER") "MCD-00072")
        (field (name "MANUFACTURER_PART_NUMBER") "RC0603JR-070RL")
        (field (name "PROVIDED_BY") "SUBCO")
      )
      (libsource (lib "MCD_PARTS_database") (part "SB_OFF"))
    )
    (comp (ref "SW1")
      (value "SWITCH_MS-22D16")
      (footprint "SWI_DHS-ELECTRONICS_MS-22D16_2P2T")
      (description "vertical slider switch 2x(A to 2B)")
      (fields
        (field (name "INTERNAL_PART_NUMBER") "MCD-01180")
        (field (name "ALTIUM_VALUE") "MS-22D16")
        (field (name "MANUFACTURER_PART_NUMBER") "MS-22D16")
        (field (name "PROVIDED_BY") "SUBCO")
      )
      (libsource (lib "MCD_PARTS_database") (part "SWITCH_MS-22D16"))
    )
    (comp (ref "SW2")
      (value "SWITCH_SS42D02")
      (footprint "SWI_DHS-ELECTRONICS_SS42D02_4P2T")
      (description "Vertical slide switch 4x (A to 2B)")
      (fields
        (field (name "INTERNAL_PART_NUMBER") "MCD-01179")
        (field (name "ALTIUM_VALUE") "SS42D02")
        (field (name "MANUFACTURER_PART_NUMBER") "SS42D02")
        (field (name "PROVIDED_BY") "SUBCO")
      )
      (libsource (lib "MCD_PARTS_database") (part "SWITCH_SS42D02"))
    )
    (comp (ref "SW3")
      (value "SWITCH_SS42D02")
      (footprint "SWI_DHS-ELECTRONICS_SS42D02_4P2T")
      (description "Vertical slide switch 4x (A to 2B)")
      (fields
        (field (name "INTERNAL_PART_NUMBER") "MCD-01179")
        (field (name "ALTIUM_VALUE") "SS42D02")
        (field (name "MANUFACTURER_PART_NUMBER") "SS42D02")
        (field (name "PROVIDED_BY") "SUBCO")
      )
      (libsource (lib "MCD_PARTS_database") (part "SWITCH_SS42D02"))
    )
    (comp (ref "SW4")
      (value "SWITCH_MS-22D16")
      (footprint "SWI_DHS-ELECTRONICS_MS-22D16_2P2T")
      (description "vertical slider switch 2x(A to 2B)")
      (fields
        (field (name "INTERNAL_PART_NUMBER") "MCD-01180")
        (field (name "ALTIUM_VALUE") "MS-22D16")
        (field (name "MANUFACTURER_PART_NUMBER") "MS-22D16")
        (field (name "PROVIDED_BY") "SUBCO")
      )
      (libsource (lib "MCD_PARTS_database") (part "SWITCH_MS-22D16"))
    )
    (comp (ref "SW5")
      (value "SWITCH_SS42D02")
      (footprint "SWI_DHS-ELECTRONICS_SS42D02_4P2T")
      (description "Vertical slide switch 4x (A to 2B)")
      (fields
        (field (name "INTERNAL_PART_NUMBER") "MCD-01179")
        (field (name "ALTIUM_VALUE") "SS42D02")
        (field (name "MANUFACTURER_PART_NUMBER") "SS42D02")
        (field (name "PROVIDED_BY") "SUBCO")
      )
      (libsource (lib "MCD_PARTS_database") (part "SWITCH_SS42D02"))
    )
    (comp (ref "SW6")
      (value "SWITCH_SS42D02")
      (footprint "SWI_DHS-ELECTRONICS_SS42D02_4P2T")
      (description "Vertical slide switch 4x (A to 2B)")
      (fields
        (field (name "INTERNAL_PART_NUMBER") "MCD-01179")
        (field (name "ALTIUM_VALUE") "SS42D02")
        (field (name "MANUFACTURER_PART_NUMBER") "SS42D02")
        (field (name "PROVIDED_BY") "SUBCO")
      )
      (libsource (lib "MCD_PARTS_database") (part "SWITCH_SS42D02"))
    )
  )
  (nets
    (net (code "2") (name "/MC1_Ain") (class "Default")
      (node (ref "R64") (pin "2") (pinfunction "2_2") (pintype "passive"))
    )
    (net (code "3") (name "/MC1_Bin") (class "Default")
      (node (ref "R55") (pin "2") (pinfunction "2_2") (pintype "passive"))
    )
    (net (code "4") (name "/MC1_BusVoltage") (class "Default")
      (node (ref "C4") (pin "1") (pinfunction "1_1") (pintype "passive"))
      (node (ref "R3") (pin "2") (pinfunction "2_2") (pintype "passive"))
    )
    (net (code "5") (name "/MC1_Cin") (class "Default")
      (node (ref "R52") (pin "2") (pinfunction "2_2") (pintype "passive"))
    )
    (net (code "6") (name "/MC1_CurrentA+") (class "Default")
      (node (ref "C8") (pin "2") (pinfunction "2_2") (pintype "passive"))
      (node (ref "R2") (pin "1") (pinfunction "1_1") (pintype "passive"))
      (node (ref "SW5") (pin "2") (pintype "passive"))
    )
    (net (code "7") (name "/MC1_CurrentB+") (class "Default")
      (node (ref "C6") (pin "2") (pinfunction "2_2") (pintype "passive"))
      (node (ref "R4") (pin "1") (pinfunction "1_1") (pintype "passive"))
      (node (ref "SW5") (pin "5") (pintype "passive"))
    )
    (net (code "8") (name "/MC1_CurrentC+") (class "Default")
      (node (ref "C2") (pin "2") (pinfunction "2_2") (pintype "passive"))
      (node (ref "R6") (pin "1") (pinfunction "1_1") (pintype "passive"))
      (node (ref "SW5") (pin "8") (pintype "passive"))
    )
    (net (code "9") (name "/MC1_DissipativeBrake") (class "Default")
      (node (ref "CN2") (pin "23") (pinfunction "DISSIPATIVE_BRAKE_23") (pintype "passive"))
    )
    (net (code "10") (name "/MC1_EnA") (class "Default")
      (node (ref "C3") (pin "2") (pinfunction "2_2") (pintype "passive"))
      (node (ref "CN2") (pin "31") (pinfunction "Encoder_A_31") (pintype "output"))
      (node (ref "SB2") (pin "1") (pinfunction "1_1") (pintype "passive"))
    )
    (net (code "11") (name "/MC1_EnB") (class "Default")
      (node (ref "C9") (pin "2") (pinfunction "2_2") (pintype "passive"))
      (node (ref "CN2") (pin "33") (pinfunction "Encoder_B_33") (pintype "output"))
    )
    (net (code "12") (name "/MC1_EnIndex") (class "Default")
      (node (ref "C11") (pin "2") (pinfunction "2_2") (pintype "passive"))
      (node (ref "CN2") (pin "34") (pinfunction "Encoder_Index_34") (pintype "output"))
    )
    (net (code "13") (name "/MC1_ICL_SHUTOUT") (class "Default")
      (node (ref "CN2") (pin "21") (pinfunction "ICL_shut_out_21") (pintype "passive"))
    )
    (net (code "14") (name "/MC1_MC2_PFC_Ind") (class "Default")
      (node (ref "C29") (pin "2") (pinfunction "2_2") (pintype "passive"))
      (node (ref "C7") (pin "2") (pinfunction "2_2") (pintype "passive"))
      (node (ref "R113") (pin "2") (pinfunction "2_2") (pintype "passive"))
      (node (ref "R5") (pin "2") (pinfunction "2_2") (pintype "passive"))
    )
    (net (code "15") (name "/MC1_MC2_PFC_SD") (class "Default")
      (node (ref "R10") (pin "2") (pinfunction "2_2") (pintype "passive"))
      (node (ref "R128") (pin "2") (pinfunction "2_2") (pintype "passive"))
    )
    (net (code "16") (name "/MC1_MC2_PFC_Vac") (class "Default")
      (node (ref "C10") (pin "2") (pinfunction "2_2") (pintype "passive"))
      (node (ref "C34") (pin "2") (pinfunction "2_2") (pintype "passive"))
      (node (ref "R12") (pin "2") (pinfunction "2_2") (pintype "passive"))
      (node (ref "R155") (pin "2") (pinfunction "2_2") (pintype "passive"))
    )
    (net (code "17") (name "/MC1_MC2_PFCpwm") (class "Default")
      (node (ref "R11") (pin "1") (pinfunction "1_1") (pintype "passive"))
      (node (ref "R151") (pin "1") (pinfunction "1_1") (pintype "passive"))
    )
    (net (code "18") (name "/MC1_MC2_PFCsync") (class "Default")
      (node (ref "R126") (pin "1") (pinfunction "1_1") (pintype "passive"))
      (node (ref "R8") (pin "1") (pinfunction "1_1") (pintype "passive"))
    )
    (net (code "19") (name "/MC1_PWM_1H") (class "Default")
      (node (ref "CN2") (pin "3") (pinfunction "PWM_1H_3") (pintype "input"))
    )
    (net (code "20") (name "/MC1_PWM_1L") (class "Default")
      (node (ref "CN2") (pin "5") (pinfunction "PWM_1L_5") (pintype "input"))
    )
    (net (code "21") (name "/MC1_PWM_2H") (class "Default")
      (node (ref "CN2") (pin "7") (pinfunction "PWM_2H_7") (pintype "input"))
    )
    (net (code "22") (name "/MC1_PWM_2L") (class "Default")
      (node (ref "CN2") (pin "9") (pinfunction "PWM_2L_9") (pintype "input"))
    )
    (net (code "23") (name "/MC1_PWM_3H") (class "Default")
      (node (ref "CN2") (pin "11") (pinfunction "PWM_3H_11") (pintype "input"))
    )
    (net (code "24") (name "/MC1_PWM_3L") (class "Default")
      (node (ref "CN2") (pin "13") (pinfunction "PWM_3L_13") (pintype "input"))
    )
    (net (code "25") (name "/MC1_STOP") (class "Default")
      (node (ref "C1") (pin "2") (pinfunction "2_2") (pintype "passive"))
      (node (ref "CN2") (pin "1") (pinfunction "EMERGENCY_STOP_1") (pintype "output"))
      (node (ref "R9") (pin "1") (pinfunction "1_1") (pintype "passive"))
    )
    (net (code "26") (name "/MC1_Temp") (class "Default")
      (node (ref "C5") (pin "2") (pinfunction "2_2") (pintype "passive"))
      (node (ref "R7") (pin "2") (pinfunction "2_2") (pintype "passive"))
    )
    (net (code "27") (name "/MC2_Ain") (class "Default")
      (node (ref "R103") (pin "2") (pinfunction "2_2") (pintype "passive"))
    )
    (net (code "28") (name "/MC2_Bin") (class "Default")
      (node (ref "R99") (pin "2") (pinfunction "2_2") (pintype "passive"))
    )
    (net (code "29") (name "/MC2_BusVoltage") (class "Default")
      (node (ref "C22") (pin "1") (pinfunction "1_1") (pintype "passive"))
      (node (ref "R77") (pin "2") (pinfunction "2_2") (pintype "passive"))
    )
    (net (code "30") (name "/MC2_Cin") (class "Default")
      (node (ref "R119") (pin "2") (pinfunction "2_2") (pintype "passive"))
    )
    (net (code "31") (name "/MC2_CurrentA+") (class "Default")
      (node (ref "C23") (pin "2") (pinfunction "2_2") (pintype "passive"))
      (node (ref "R86") (pin "1") (pinfunction "1_1") (pintype "passive"))
      (node (ref "SW6") (pin "8") (pintype "passive"))
    )
    (net (code "32") (name "/MC2_CurrentB+") (class "Default")
      (node (ref "C24") (pin "2") (pinfunction "2_2") (pintype "passive"))
      (node (ref "R92") (pin "1") (pinfunction "1_1") (pintype "passive"))
      (node (ref "SW6") (pin "5") (pintype "passive"))
    )
    (net (code "33") (name "/MC2_CurrentC+") (class "Default")
      (node (ref "C26") (pin "2") (pinfunction "2_2") (pintype "passive"))
      (node (ref "R100") (pin "1") (pinfunction "1_1") (pintype "passive"))
      (node (ref "SW6") (pin "2") (pintype "passive"))
    )
    (net (code "34") (name "/MC2_DissipativeBrake") (class "Default")
      (node (ref "CN4") (pin "23") (pinfunction "DISSIPATIVE_BRAKE_23") (pintype "passive"))
    )
    (net (code "35") (name "/MC2_EnA") (class "Default")
      (node (ref "C37") (pin "2") (pinfunction "2_2") (pintype "passive"))
      (node (ref "CN4") (pin "31") (pinfunction "Encoder_A_31") (pintype "output"))
      (node (ref "SB32") (pin "1") (pinfunction "1_1") (pintype "passive"))
    )
    (net (code "36") (name "/MC2_EnB") (class "Default")
      (node (ref "C42") (pin "2") (pinfunction "2_2") (pintype "passive"))
      (node (ref "CN4") (pin "33") (pinfunction "Encoder_B_33") (pintype "output"))
    )
    (net (code "37") (name "/MC2_EnIndex") (class "Default")
      (node (ref "C39") (pin "2") (pinfunction "2_2") (pintype "passive"))
      (node (ref "CN4") (pin "34") (pinfunction "Encoder_Index_34") (pintype "output"))
    )
    (net (code "38") (name "/MC2_ICL_SHUTOUT") (class "Default")
      (node (ref "CN4") (pin "21") (pinfunction "ICL_shut_out_21") (pintype "passive"))
    )
    (net (code "39") (name "/MC2_PWM_1H") (class "Default")
      (node (ref "CN4") (pin "3") (pinfunction "PWM_1H_3") (pintype "input"))
    )
    (net (code "40") (name "/MC2_PWM_1L") (class "Default")
      (node (ref "CN4") (pin "5") (pinfunction "PWM_1L_5") (pintype "input"))
    )
    (net (code "41") (name "/MC2_PWM_2H") (class "Default")
      (node (ref "CN4") (pin "7") (pinfunction "PWM_2H_7") (pintype "input"))
    )
    (net (code "42") (name "/MC2_PWM_2L") (class "Default")
      (node (ref "CN4") (pin "9") (pinfunction "PWM_2L_9") (pintype "input"))
    )
    (net (code "43") (name "/MC2_PWM_3H") (class "Default")
      (node (ref "CN4") (pin "11") (pinfunction "PWM_3H_11") (pintype "input"))
    )
    (net (code "44") (name "/MC2_PWM_3L") (class "Default")
      (node (ref "CN4") (pin "13") (pinfunction "PWM_3L_13") (pintype "input"))
    )
    (net (code "45") (name "/MC2_STOP") (class "Default")
      (node (ref "R21") (pin "1") (pinfunction "1_1") (pintype "passive"))
    )
    (net (code "46") (name "/MC2_Temp") (class "Default")
      (node (ref "C31") (pin "2") (pinfunction "2_2") (pintype "passive"))
      (node (ref "R120") (pin "2") (pinfunction "2_2") (pintype "passive"))
    )
    (net (code "47") (name "/MC_DAC_OUT1") (class "Default")
      (node (ref "SW3") (pin "3") (pintype "passive"))
      (node (ref "SW3") (pin "6") (pintype "passive"))
      (node (ref "SW4") (pin "2") (pintype "passive"))
    )
    (net (code "48") (name "/MC_DAC_OUT2") (class "Default")
      (node (ref "CN32") (pin "1") (pinfunction "COMMON_1") (pintype "passive"))
    )
    (net (code "49") (name "/OPAMP1_INN") (class "Default")
      (node (ref "C20") (pin "1") (pinfunction "1_1") (pintype "passive"))
      (node (ref "R65") (pin "2") (pinfunction "2_2") (pintype "passive"))
      (node (ref "R67") (pin "2") (pinfunction "2_2") (pintype "passive"))
    )
    (net (code "50") (name "/OPAMP1_INP") (class "Default")
      (node (ref "R61") (pin "2") (pinfunction "2_2") (pintype "passive"))
    )
    (net (code "51") (name "/OPAMP1_OUT") (class "Default")
      (node (ref "C20") (pin "2") (pinfunction "2_2") (pintype "passive"))
      (node (ref "R67") (pin "1") (pinfunction "1_1") (pintype "passive"))
    )
    (net (code "52") (name "/OPAMP2_IN1P") (class "Default")
      (node (ref "R31") (pin "2") (pinfunction "2_2") (pintype "passive"))
    )
    (net (code "53") (name "/OPAMP2_IN2P") (class "Default")
      (node (ref "C15") (pin "1") (pinfunction "1_1") (pintype "passive"))
      (node (ref "R24") (pin "2") (pinfunction "2_2") (pintype "passive"))
      (node (ref "R25") (pin "1") (pinfunction "1_1") (pintype "passive"))
    )
    (net (code "54") (name "/OPAMP2_INN") (class "Default")
      (node (ref "C19") (pin "1") (pinfunction "1_1") (pintype "passive"))
      (node (ref "R56") (pin "2") (pinfunction "2_2") (pintype "passive"))
      (node (ref "R57") (pin "2") (pinfunction "2_2") (pintype "passive"))
    )
    (net (code "55") (name "/OPAMP2_OUT") (class "Default")
      (node (ref "C19") (pin "2") (pinfunction "2_2") (pintype "passive"))
      (node (ref "R57") (pin "1") (pinfunction "1_1") (pintype "passive"))
    )
    (net (code "56") (name "/OPAMP3_INN") (class "Default")
      (node (ref "C27") (pin "1") (pinfunction "1_1") (pintype "passive"))
      (node (ref "R105") (pin "2") (pinfunction "2_2") (pintype "passive"))
      (node (ref "R106") (pin "2") (pinfunction "2_2") (pintype "passive"))
    )
    (net (code "57") (name "/OPAMP3_INP") (class "Default")
      (node (ref "R125") (pin "2") (pinfunction "2_2") (pintype "passive"))
    )
    (net (code "58") (name "/OPAMP3_OUT") (class "Default")
      (node (ref "C27") (pin "2") (pinfunction "2_2") (pintype "passive"))
      (node (ref "R105") (pin "1") (pinfunction "1_1") (pintype "passive"))
    )
    (net (code "59") (name "/OPAMP4_IN1P") (class "Default")
      (node (ref "C14") (pin "1") (pinfunction "1_1") (pintype "passive"))
      (node (ref "R20") (pin "1") (pinfunction "1_1") (pintype "passive"))
      (node (ref "R22") (pin "2") (pinfunction "2_2") (pintype "passive"))
    )
    (net (code "60") (name "/OPAMP4_IN2P") (class "Default")
      (node (ref "R91") (pin "2") (pinfunction "2_2") (pintype "passive"))
    )
    (net (code "61") (name "/OPAMP4_INN") (class "Default")
      (node (ref "C17") (pin "1") (pinfunction "1_1") (pintype "passive"))
      (node (ref "R32") (pin "2") (pinfunction "2_2") (pintype "passive"))
      (node (ref "R33") (pin "2") (pinfunction "2_2") (pintype "passive"))
    )
    (net (code "62") (name "/OPAMP4_OUT") (class "Default")
      (node (ref "C17") (pin "2") (pinfunction "2_2") (pintype "passive"))
      (node (ref "R33") (pin "1") (pinfunction "1_1") (pintype "passive"))
    )
    (net (code "64") (name "3V3") (class "Default")
      (node (ref "CN2") (pin "28") (pinfunction "3.3V_Power_28") (pintype "power_in"))
      (node (ref "CN4") (pin "28") (pinfunction "3.3V_Power_28") (pintype "power_in"))
      (node (ref "R23") (pin "2") (pinfunction "2_2") (pintype "passive"))
      (node (ref "R9") (pin "2") (pinfunction "2_2") (pintype "passive"))
      (node (ref "SW2") (pin "1") (pintype "passive"))
      (node (ref "SW2") (pin "4") (pintype "passive"))
      (node (ref "SW2") (pin "7") (pintype "passive"))
      (node (ref "SW3") (pin "1") (pintype "passive"))
      (node (ref "SW3") (pin "4") (pintype "passive"))
      (node (ref "SW3") (pin "7") (pintype "passive"))
    )
    (net (code "65") (name "5V") (class "Default")
      (node (ref "CN2") (pin "25") (pinfunction "+5V_POWER_25") (pintype "power_in"))
      (node (ref "CN4") (pin "25") (pinfunction "+5V_POWER_25") (pintype "power_in"))
    )
    (net (code "66") (name "GND") (class "Default")
      (node (ref "C1") (pin "1") (pinfunction "1_1") (pintype "passive"))
      (node (ref "C10") (pin "1") (pinfunction "1_1") (pintype "passive"))
      (node (ref "C11") (pin "1") (pinfunction "1_1") (pintype "passive"))
      (node (ref "C12") (pin "1") (pinfunction "1_1") (pintype "passive"))
      (node (ref "C14") (pin "2") (pinfunction "2_2") (pintype "passive"))
      (node (ref "C15") (pin "2") (pinfunction "2_2") (pintype "passive"))
      (node (ref "C16") (pin "1") (pinfunction "1_1") (pintype "passive"))
      (node (ref "C18") (pin "2") (pinfunction "2_2") (pintype "passive"))
      (node (ref "C2") (pin "1") (pinfunction "1_1") (pintype "passive"))
      (node (ref "C21") (pin "2") (pinfunction "2_2") (pintype "passive"))
      (node (ref "C22") (pin "2") (pinfunction "2_2") (pintype "passive"))
      (node (ref "C23") (pin "1") (pinfunction "1_1") (pintype "passive"))
      (node (ref "C24") (pin "1") (pinfunction "1_1") (pintype "passive"))
      (node (ref "C25") (pin "2") (pinfunction "2_2") (pintype "passive"))
      (node (ref "C26") (pin "1") (pinfunction "1_1") (pintype "passive"))
      (node (ref "C29") (pin "1") (pinfunction "1_1") (pintype "passive"))
      (node (ref "C3") (pin "1") (pinfunction "1_1") (pintype "passive"))
      (node (ref "C31") (pin "1") (pinfunction "1_1") (pintype "passive"))
      (node (ref "C32") (pin "2") (pinfunction "2_2") (pintype "passive"))
      (node (ref "C34") (pin "1") (pinfunction "1_1") (pintype "passive"))
      (node (ref "C37") (pin "1") (pinfunction "1_1") (pintype "passive"))
      (node (ref "C38") (pin "1") (pinfunction "1_1") (pintype "passive"))
      (node (ref "C39") (pin "1") (pinfunction "1_1") (pintype "passive"))
      (node (ref "C4") (pin "2") (pinfunction "2_2") (pintype "passive"))
      (node (ref "C42") (pin "1") (pinfunction "1_1") (pintype "passive"))
      (node (ref "C5") (pin "1") (pinfunction "1_1") (pintype "passive"))
      (node (ref "C6") (pin "1") (pinfunction "1_1") (pintype "passive"))
      (node (ref "C7") (pin "1") (pinfunction "1_1") (pintype "passive"))
      (node (ref "C8") (pin "1") (pinfunction "1_1") (pintype "passive"))
      (node (ref "C9") (pin "1") (pinfunction "1_1") (pintype "passive"))
      (node (ref "CN2") (pin "10") (pinfunction "GND_10") (pintype "power_in"))
      (node (ref "CN2") (pin "12") (pinfunction "GND_12") (pintype "power_in"))
      (node (ref "CN2") (pin "16") (pinfunction "PHASE_A_CURRENT_-_16") (pintype "power_in"))
      (node (ref "CN2") (pin "18") (pinfunction "PHASE_B_CURRENT_-_18") (pintype "power_in"))
      (node (ref "CN2") (pin "2") (pinfunction "GND_2") (pintype "power_in"))
      (node (ref "CN2") (pin "20") (pinfunction "PHASE_C_CURRENT_-_20") (pintype "power_in"))
      (node (ref "CN2") (pin "22") (pinfunction "GND_22") (pintype "power_in"))
      (node (ref "CN2") (pin "4") (pinfunction "GND_4") (pintype "power_in"))
      (node (ref "CN2") (pin "6") (pinfunction "GND_6") (pintype "power_in"))
      (node (ref "CN2") (pin "8") (pinfunction "GND_8") (pintype "power_in"))
      (node (ref "CN4") (pin "16") (pinfunction "PHASE_A_CURRENT_-_16") (pintype "power_in"))
      (node (ref "CN4") (pin "18") (pinfunction "PHASE_B_CURRENT_-_18") (pintype "power_in"))
      (node (ref "CN4") (pin "20") (pinfunction "PHASE_C_CURRENT_-_20") (pintype "power_in"))
      (node (ref "CN4") (pin "22") (pinfunction "GND_22") (pintype "power_in"))
      (node (ref "R106") (pin "1") (pinfunction "1_1") (pintype "passive"))
      (node (ref "R18") (pin "2") (pinfunction "2_2") (pintype "passive"))
      (node (ref "R32") (pin "1") (pinfunction "1_1") (pintype "passive"))
      (node (ref "R56") (pin "1") (pinfunction "1_1") (pintype "passive"))
      (node (ref "R65") (pin "1") (pinfunction "1_1") (pintype "passive"))
    )
    (net (code "67") (name "Net-(C12-Pad2)") (class "Default")
      (node (ref "C12") (pin "2") (pinfunction "2_2") (pintype "passive"))
      (node (ref "SB2") (pin "2") (pinfunction "2_2") (pintype "passive"))
    )
    (net (code "68") (name "Net-(C18-Pad1)") (class "Default")
      (node (ref "C18") (pin "1") (pinfunction "1_1") (pintype "passive"))
      (node (ref "R31") (pin "1") (pinfunction "1_1") (pintype "passive"))
      (node (ref "R51") (pin "1") (pinfunction "1_1") (pintype "passive"))
      (node (ref "R59") (pin "2") (pinfunction "2_2") (pintype "passive"))
    )
    (net (code "69") (name "Net-(C21-Pad1)") (class "Default")
      (node (ref "C21") (pin "1") (pinfunction "1_1") (pintype "passive"))
      (node (ref "R61") (pin "1") (pinfunction "1_1") (pintype "passive"))
      (node (ref "R66") (pin "1") (pinfunction "1_1") (pintype "passive"))
      (node (ref "R76") (pin "2") (pinfunction "2_2") (pintype "passive"))
    )
    (net (code "70") (name "Net-(C25-Pad1)") (class "Default")
      (node (ref "C25") (pin "1") (pinfunction "1_1") (pintype "passive"))
      (node (ref "R104") (pin "2") (pinfunction "2_2") (pintype "passive"))
      (node (ref "R91") (pin "1") (pinfunction "1_1") (pintype "passive"))
      (node (ref "R95") (pin "1") (pinfunction "1_1") (pintype "passive"))
    )
    (net (code "71") (name "Net-(C32-Pad1)") (class "Default")
      (node (ref "C32") (pin "1") (pinfunction "1_1") (pintype "passive"))
      (node (ref "R115") (pin "2") (pinfunction "2_2") (pintype "passive"))
      (node (ref "R122") (pin "1") (pinfunction "1_1") (pintype "passive"))
      (node (ref "R125") (pin "1") (pinfunction "1_1") (pintype "passive"))
    )
    (net (code "72") (name "Net-(C38-Pad2)") (class "Default")
      (node (ref "C38") (pin "2") (pinfunction "2_2") (pintype "passive"))
      (node (ref "SB32") (pin "2") (pinfunction "2_2") (pintype "passive"))
    )
    (net (code "73") (name "Net-(CN2-BUS_VOLTAGE)") (class "Default")
      (node (ref "CN2") (pin "14") (pinfunction "BUS_VOLTAGE_14") (pintype "output"))
      (node (ref "R3") (pin "1") (pinfunction "1_1") (pintype "passive"))
    )
    (net (code "74") (name "Net-(CN2-Heatsink_Temperature)") (class "Default")
      (node (ref "CN2") (pin "26") (pinfunction "Heatsink_Temperature_26") (pintype "output"))
      (node (ref "R7") (pin "1") (pinfunction "1_1") (pintype "passive"))
    )
    (net (code "75") (name "Net-(CN2-PFC_Inductor_current)") (class "Default")
      (node (ref "CN2") (pin "24") (pinfunction "PFC_Inductor_current_24") (pintype "passive"))
      (node (ref "R5") (pin "1") (pinfunction "1_1") (pintype "passive"))
    )
    (net (code "76") (name "Net-(CN2-PFC_PWM)") (class "Default")
      (node (ref "CN2") (pin "29") (pinfunction "PFC_PWM_29") (pintype "input"))
      (node (ref "R11") (pin "2") (pinfunction "2_2") (pintype "passive"))
    )
    (net (code "77") (name "Net-(CN2-PFC_SYNC)") (class "Default")
      (node (ref "CN2") (pin "27") (pinfunction "PFC_SYNC_27") (pintype "passive"))
      (node (ref "R8") (pin "2") (pinfunction "2_2") (pintype "passive"))
    )
    (net (code "78") (name "Net-(CN2-PFC_Shut_down)") (class "Default")
      (node (ref "CN2") (pin "30") (pinfunction "PFC_Shut_down_30") (pintype "passive"))
      (node (ref "R10") (pin "1") (pinfunction "1_1") (pintype "passive"))
    )
    (net (code "79") (name "Net-(CN2-PFC_Vac)") (class "Default")
      (node (ref "CN2") (pin "32") (pinfunction "PFC_Vac_32") (pintype "passive"))
      (node (ref "R12") (pin "1") (pinfunction "1_1") (pintype "passive"))
    )
    (net (code "80") (name "Net-(CN2-PHASE_A_CURRENT_+)") (class "Default")
      (node (ref "CN2") (pin "15") (pinfunction "PHASE_A_CURRENT_+_15") (pintype "output"))
      (node (ref "R2") (pin "2") (pinfunction "2_2") (pintype "passive"))
    )
    (net (code "81") (name "Net-(CN2-PHASE_B_CURRENT_+)") (class "Default")
      (node (ref "CN2") (pin "17") (pinfunction "PHASE_B_CURRENT_+_17") (pintype "output"))
      (node (ref "R4") (pin "2") (pinfunction "2_2") (pintype "passive"))
    )
    (net (code "82") (name "Net-(CN2-PHASE_C_CURRENT_+)") (class "Default")
      (node (ref "CN2") (pin "19") (pinfunction "PHASE_C_CURRENT_+_19") (pintype "output"))
      (node (ref "R6") (pin "2") (pinfunction "2_2") (pintype "passive"))
    )
    (net (code "83") (name "Net-(CN4-BUS_VOLTAGE)") (class "Default")
      (node (ref "CN4") (pin "14") (pinfunction "BUS_VOLTAGE_14") (pintype "output"))
      (node (ref "R77") (pin "1") (pinfunction "1_1") (pintype "passive"))
    )
    (net (code "84") (name "Net-(CN4-EMERGENCY_STOP)") (class "Default")
      (node (ref "C16") (pin "2") (pinfunction "2_2") (pintype "passive"))
      (node (ref "CN4") (pin "1") (pinfunction "EMERGENCY_STOP_1") (pintype "output"))
      (node (ref "R21") (pin "2") (pinfunction "2_2") (pintype "passive"))
      (node (ref "R23") (pin "1") (pinfunction "1_1") (pintype "passive"))
    )
    (net (code "85") (name "Net-(CN4-GND-Pad10)") (class "Default")
      (node (ref "CN4") (pin "10") (pinfunction "GND_10") (pintype "power_in"))
      (node (ref "CN4") (pin "12") (pinfunction "GND_12") (pintype "power_in"))
      (node (ref "CN4") (pin "2") (pinfunction "GND_2") (pintype "power_in"))
      (node (ref "CN4") (pin "4") (pinfunction "GND_4") (pintype "power_in"))
      (node (ref "CN4") (pin "6") (pinfunction "GND_6") (pintype "power_in"))
      (node (ref "CN4") (pin "8") (pinfunction "GND_8") (pintype "power_in"))
      (node (ref "R18") (pin "1") (pinfunction "1_1") (pintype "passive"))
    )
    (net (code "86") (name "Net-(CN4-Heatsink_Temperature)") (class "Default")
      (node (ref "CN4") (pin "26") (pinfunction "Heatsink_Temperature_26") (pintype "output"))
      (node (ref "R120") (pin "1") (pinfunction "1_1") (pintype "passive"))
    )
    (net (code "87") (name "Net-(CN4-PFC_Inductor_current)") (class "Default")
      (node (ref "CN4") (pin "24") (pinfunction "PFC_Inductor_current_24") (pintype "passive"))
      (node (ref "R113") (pin "1") (pinfunction "1_1") (pintype "passive"))
    )
    (net (code "88") (name "Net-(CN4-PFC_PWM)") (class "Default")
      (node (ref "CN4") (pin "29") (pinfunction "PFC_PWM_29") (pintype "input"))
      (node (ref "R151") (pin "2") (pinfunction "2_2") (pintype "passive"))
    )
    (net (code "89") (name "Net-(CN4-PFC_SYNC)") (class "Default")
      (node (ref "CN4") (pin "27") (pinfunction "PFC_SYNC_27") (pintype "passive"))
      (node (ref "R126") (pin "2") (pinfunction "2_2") (pintype "passive"))
    )
    (net (code "90") (name "Net-(CN4-PFC_Shut_down)") (class "Default")
      (node (ref "CN4") (pin "30") (pinfunction "PFC_Shut_down_30") (pintype "passive"))
      (node (ref "R128") (pin "1") (pinfunction "1_1") (pintype "passive"))
    )
    (net (code "91") (name "Net-(CN4-PFC_Vac)") (class "Default")
      (node (ref "CN4") (pin "32") (pinfunction "PFC_Vac_32") (pintype "passive"))
      (node (ref "R155") (pin "1") (pinfunction "1_1") (pintype "passive"))
    )
    (net (code "92") (name "Net-(CN4-PHASE_A_CURRENT_+)") (class "Default")
      (node (ref "CN4") (pin "15") (pinfunction "PHASE_A_CURRENT_+_15") (pintype "output"))
      (node (ref "R86") (pin "2") (pinfunction "2_2") (pintype "passive"))
    )
    (net (code "93") (name "Net-(CN4-PHASE_B_CURRENT_+)") (class "Default")
      (node (ref "CN4") (pin "17") (pinfunction "PHASE_B_CURRENT_+_17") (pintype "output"))
      (node (ref "R92") (pin "2") (pinfunction "2_2") (pintype "passive"))
    )
    (net (code "94") (name "Net-(CN4-PHASE_C_CURRENT_+)") (class "Default")
      (node (ref "CN4") (pin "19") (pinfunction "PHASE_C_CURRENT_+_19") (pintype "output"))
      (node (ref "R100") (pin "2") (pinfunction "2_2") (pintype "passive"))
    )
    (net (code "95") (name "Net-(CN32-NO)") (class "Default")
      (node (ref "CN32") (pin "2") (pinfunction "NO_2") (pintype "passive"))
      (node (ref "SW2") (pin "6") (pintype "passive"))
      (node (ref "SW2") (pin "9") (pintype "passive"))
      (node (ref "SW4") (pin "5") (pintype "passive"))
    )
    (net (code "96") (name "Net-(R20-Pad2)") (class "Default")
      (node (ref "R20") (pin "2") (pinfunction "2_2") (pintype "passive"))
      (node (ref "SW2") (pin "2") (pintype "passive"))
    )
    (net (code "97") (name "Net-(R22-Pad1)") (class "Default")
      (node (ref "R22") (pin "1") (pinfunction "1_1") (pintype "passive"))
      (node (ref "SW1") (pin "5") (pintype "passive"))
    )
    (net (code "98") (name "Net-(R24-Pad1)") (class "Default")
      (node (ref "R24") (pin "1") (pinfunction "1_1") (pintype "passive"))
      (node (ref "SW1") (pin "2") (pintype "passive"))
    )
    (net (code "99") (name "Net-(R25-Pad2)") (class "Default")
      (node (ref "R25") (pin "2") (pinfunction "2_2") (pintype "passive"))
      (node (ref "SW3") (pin "8") (pintype "passive"))
    )
    (net (code "100") (name "Net-(R51-Pad2)") (class "Default")
      (node (ref "R51") (pin "2") (pinfunction "2_2") (pintype "passive"))
      (node (ref "SW3") (pin "5") (pintype "passive"))
    )
    (net (code "101") (name "Net-(R52-Pad1)") (class "Default")
      (node (ref "R52") (pin "1") (pinfunction "1_1") (pintype "passive"))
      (node (ref "SW5") (pin "9") (pintype "passive"))
    )
    (net (code "102") (name "Net-(R55-Pad1)") (class "Default")
      (node (ref "R55") (pin "1") (pinfunction "1_1") (pintype "passive"))
      (node (ref "SW5") (pin "6") (pintype "passive"))
    )
    (net (code "103") (name "Net-(R58-Pad1)") (class "Default")
      (node (ref "R58") (pin "1") (pinfunction "1_1") (pintype "passive"))
      (node (ref "SB14") (pin "1") (pinfunction "1_1") (pintype "passive"))
      (node (ref "SW5") (pin "4") (pintype "passive"))
    )
    (net (code "104") (name "Net-(R58-Pad2)") (class "Default")
      (node (ref "R58") (pin "2") (pinfunction "2_2") (pintype "passive"))
      (node (ref "R59") (pin "1") (pinfunction "1_1") (pintype "passive"))
    )
    (net (code "105") (name "Net-(R64-Pad1)") (class "Default")
      (node (ref "R64") (pin "1") (pinfunction "1_1") (pintype "passive"))
      (node (ref "SW5") (pin "3") (pintype "passive"))
    )
    (net (code "106") (name "Net-(R66-Pad2)") (class "Default")
      (node (ref "R66") (pin "2") (pinfunction "2_2") (pintype "passive"))
      (node (ref "SW3") (pin "2") (pintype "passive"))
    )
    (net (code "107") (name "Net-(R72-Pad1)") (class "Default")
      (node (ref "R72") (pin "1") (pinfunction "1_1") (pintype "passive"))
      (node (ref "SW5") (pin "1") (pintype "passive"))
    )
    (net (code "108") (name "Net-(R72-Pad2)") (class "Default")
      (node (ref "R72") (pin "2") (pinfunction "2_2") (pintype "passive"))
      (node (ref "R76") (pin "1") (pinfunction "1_1") (pintype "passive"))
      (node (ref "SB14") (pin "2") (pinfunction "2_2") (pintype "passive"))
    )
    (net (code "109") (name "Net-(R95-Pad2)") (class "Default")
      (node (ref "R95") (pin "2") (pinfunction "2_2") (pintype "passive"))
      (node (ref "SW2") (pin "5") (pintype "passive"))
    )
    (net (code "110") (name "Net-(R99-Pad1)") (class "Default")
      (node (ref "R99") (pin "1") (pinfunction "1_1") (pintype "passive"))
      (node (ref "SW6") (pin "6") (pintype "passive"))
    )
    (net (code "111") (name "Net-(R103-Pad1)") (class "Default")
      (node (ref "R103") (pin "1") (pinfunction "1_1") (pintype "passive"))
      (node (ref "SW6") (pin "9") (pintype "passive"))
    )
    (net (code "112") (name "Net-(R104-Pad1)") (class "Default")
      (node (ref "R104") (pin "1") (pinfunction "1_1") (pintype "passive"))
      (node (ref "R110") (pin "2") (pinfunction "2_2") (pintype "passive"))
    )
    (net (code "113") (name "Net-(R110-Pad1)") (class "Default")
      (node (ref "R110") (pin "1") (pinfunction "1_1") (pintype "passive"))
      (node (ref "SB19") (pin "1") (pinfunction "1_1") (pintype "passive"))
      (node (ref "SW6") (pin "4") (pintype "passive"))
    )
    (net (code "114") (name "Net-(R114-Pad1)") (class "Default")
      (node (ref "R114") (pin "1") (pinfunction "1_1") (pintype "passive"))
      (node (ref "SW6") (pin "7") (pintype "passive"))
    )
    (net (code "115") (name "Net-(R114-Pad2)") (class "Default")
      (node (ref "R114") (pin "2") (pinfunction "2_2") (pintype "passive"))
      (node (ref "R115") (pin "1") (pinfunction "1_1") (pintype "passive"))
      (node (ref "SB19") (pin "2") (pinfunction "2_2") (pintype "passive"))
    )
    (net (code "116") (name "Net-(R119-Pad1)") (class "Default")
      (node (ref "R119") (pin "1") (pinfunction "1_1") (pintype "passive"))
      (node (ref "SW6") (pin "3") (pintype "passive"))
    )
    (net (code "117") (name "Net-(R122-Pad2)") (class "Default")
      (node (ref "R122") (pin "2") (pinfunction "2_2") (pintype "passive"))
      (node (ref "SW2") (pin "8") (pintype "passive"))
    )
    (net (code "118") (name "Net-(SW1-Pad1)") (class "Default")
      (node (ref "SW1") (pin "1") (pintype "passive"))
      (node (ref "SW1") (pin "6") (pintype "passive"))
      (node (ref "SW5") (pin "7") (pintype "passive"))
    )
    (net (code "119") (name "Net-(SW1-Pad3)") (class "Default")
      (node (ref "SW1") (pin "3") (pintype "passive"))
      (node (ref "SW1") (pin "4") (pintype "passive"))
      (node (ref "SW6") (pin "1") (pintype "passive"))
    )
    (net (code "120") (name "Net-(SW2-Pad3)") (class "Default")
      (node (ref "SW2") (pin "3") (pintype "passive"))
      (node (ref "SW4") (pin "3") (pintype "passive"))
      (node (ref "SW4") (pin "4") (pintype "passive"))
    )
    (net (code "121") (name "Net-(SW3-Pad9)") (class "Default")
      (node (ref "SW3") (pin "9") (pintype "passive"))
      (node (ref "SW4") (pin "1") (pintype "passive"))
      (node (ref "SW4") (pin "6") (pintype "passive"))
    )
    (net (code "122") (name "unconnected-(SW2-Pad10)") (class "Default")
      (node (ref "SW2") (pin "10") (pintype "passive+no_connect"))
    )
    (net (code "123") (name "unconnected-(SW2-Pad11)") (class "Default")
      (node (ref "SW2") (pin "11") (pintype "passive+no_connect"))
    )
    (net (code "124") (name "unconnected-(SW2-Pad12)") (class "Default")
      (node (ref "SW2") (pin "12") (pintype "passive+no_connect"))
    )
    (net (code "125") (name "unconnected-(SW3-Pad10)") (class "Default")
      (node (ref "SW3") (pin "10") (pintype "passive+no_connect"))
    )
    (net (code "126") (name "unconnected-(SW3-Pad11)") (class "Default")
      (node (ref "SW3") (pin "11") (pintype "passive+no_connect"))
    )
    (net (code "127") (name "unconnected-(SW3-Pad12)") (class "Default")
      (node (ref "SW3") (pin "12") (pintype "passive+no_connect"))
    )
    (net (code "128") (name "unconnected-(SW5-Pad10)") (class "Default")
      (node (ref "SW5") (pin "10") (pintype "passive+no_connect"))
    )
    (net (code "129") (name "unconnected-(SW5-Pad11)") (class "Default")
      (node (ref "SW5") (pin "11") (pintype "passive+no_connect"))
    )
    (net (code "130") (name "unconnected-(SW5-Pad12)") (class "Default")
      (node (ref "SW5") (pin "12") (pintype "passive+no_connect"))
    )
    (net (code "131") (name "unconnected-(SW6-Pad10)") (class "Default")
      (node (ref "SW6") (pin "10") (pintype "passive+no_connect"))
    )
    (net (code "132") (name "unconnected-(SW6-Pad11)") (class "Default")
      (node (ref "SW6") (pin "11") (pintype "passive+no_connect"))
    )
    (net (code "133") (name "unconnected-(SW6-Pad12)") (class "Default")
      (node (ref "SW6") (pin "12") (pintype "passive+no_connect"))
    )
  )
)
